# Control.net
KiCad netlist of a schematic drawn in Altium Designer
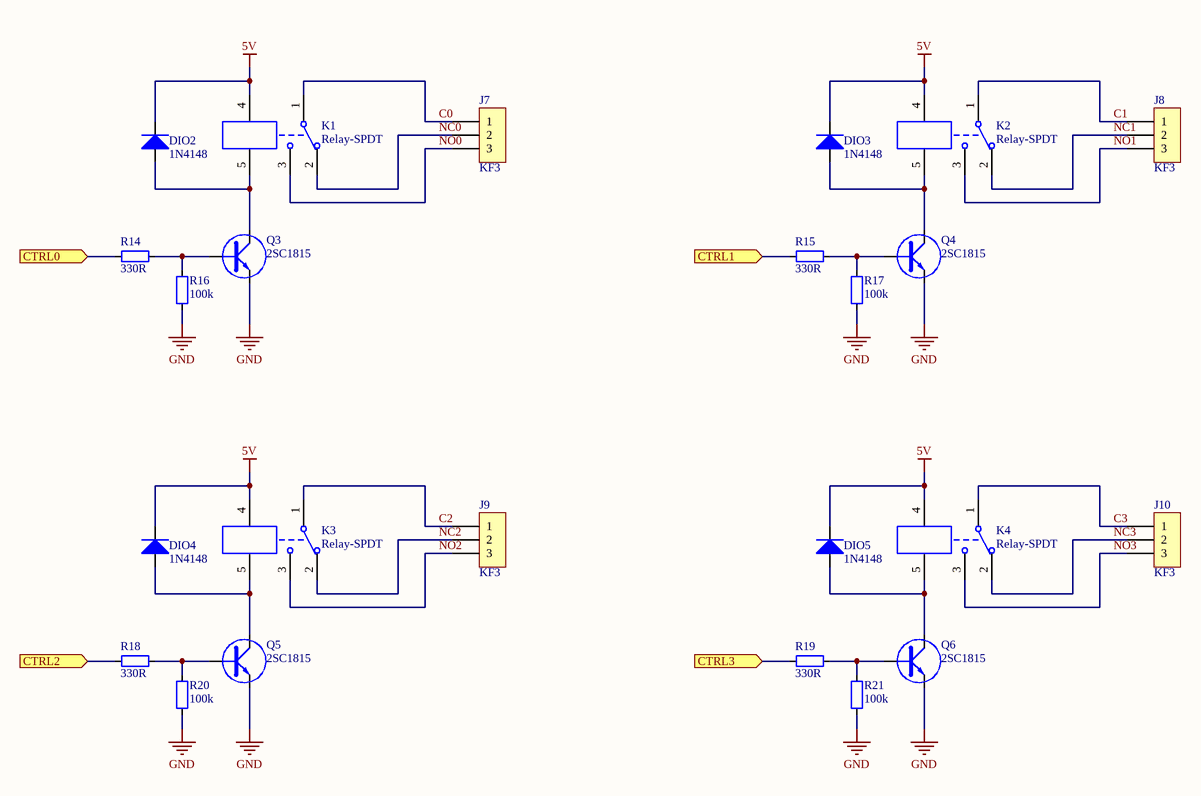
[diagram p0: Control.SchDoc]

(export (version "E")
  (design (tool "Eeschema 10.0.6"))
  (components
    (comp (ref "DIO2")
      (value "1N4148")
      (footprint "DIO-SMD-106")
      (description "Default Diode")
      (fields (field (name "PUBLISHER") "Altium Limited"))
      (libsource (lib "Ven_lib") (part "Diode SMD"))
    )
    (comp (ref "DIO3")
      (value "1N4148")
      (footprint "DIO-SMD-106")
      (description "Default Diode")
      (fields (field (name "PUBLISHER") "Altium Limited"))
      (libsource (lib "Ven_lib") (part "Diode SMD"))
    )
    (comp (ref "DIO4")
      (value "1N4148")
      (footprint "DIO-SMD-106")
      (description "Default Diode")
      (fields (field (name "PUBLISHER") "Altium Limited"))
      (libsource (lib "Ven_lib") (part "Diode SMD"))
    )
    (comp (ref "DIO5")
      (value "1N4148")
      (footprint "DIO-SMD-106")
      (description "Default Diode")
      (fields (field (name "PUBLISHER") "Altium Limited"))
      (libsource (lib "Ven_lib") (part "Diode SMD"))
    )
    (comp (ref "J7")
      (value "KF3")
      (footprint "KF3-5.08")
      (fields
        (field (name "MANUFACTURER") "Würth Elektronik eiSos GmbH")
        (field (name "PARTNO") "691103110003")
        (field (name "CREATED BY") "Karrer Zheng")
      )
      (libsource (lib "My Library") (part "KF3"))
    )
    (comp (ref "J8")
      (value "KF3")
      (footprint "KF3-5.08")
      (fields
        (field (name "MANUFACTURER") "Würth Elektronik eiSos GmbH")
        (field (name "PARTNO") "691103110003")
        (field (name "CREATED BY") "Karrer Zheng")
      )
      (libsource (lib "My Library") (part "KF3"))
    )
    (comp (ref "J9")
      (value "KF3")
      (footprint "KF3-5.08")
      (fields
        (field (name "MANUFACTURER") "Würth Elektronik eiSos GmbH")
        (field (name "PARTNO") "691103110003")
        (field (name "CREATED BY") "Karrer Zheng")
      )
      (libsource (lib "My Library") (part "KF3"))
    )
    (comp (ref "J10")
      (value "KF3")
      (footprint "KF3-5.08")
      (fields
        (field (name "MANUFACTURER") "Würth Elektronik eiSos GmbH")
        (field (name "PARTNO") "691103110003")
        (field (name "CREATED BY") "Karrer Zheng")
      )
      (libsource (lib "My Library") (part "KF3"))
    )
    (comp (ref "K1")
      (value "Relay-SPDT")
      (footprint "RELAY5PIN-10A")
      (description "Single-Pole Dual-Throw Relay")
      (fields (field (name "PUBLISHER") "Altium Limited"))
      (libsource (lib "My Library") (part "Relay-SPDT"))
    )
    (comp (ref "K2")
      (value "Relay-SPDT")
      (footprint "RELAY5PIN-10A")
      (description "Single-Pole Dual-Throw Relay")
      (fields (field (name "PUBLISHER") "Altium Limited"))
      (libsource (lib "My Library") (part "Relay-SPDT"))
    )
    (comp (ref "K3")
      (value "Relay-SPDT")
      (footprint "RELAY5PIN-10A")
      (description "Single-Pole Dual-Throw Relay")
      (fields (field (name "PUBLISHER") "Altium Limited"))
      (libsource (lib "My Library") (part "Relay-SPDT"))
    )
    (comp (ref "K4")
      (value "Relay-SPDT")
      (footprint "RELAY5PIN-10A")
      (description "Single-Pole Dual-Throw Relay")
      (fields (field (name "PUBLISHER") "Altium Limited"))
      (libsource (lib "My Library") (part "Relay-SPDT"))
    )
    (comp (ref "Q3")
      (value "2SC1815")
      (footprint "SOT23")
      (description "NPN 600mW, ECB")
      (libsource (lib "My Library") (part "2SC1815"))
    )
    (comp (ref "Q4")
      (value "2SC1815")
      (footprint "SOT23")
      (description "NPN 600mW, ECB")
      (libsource (lib "My Library") (part "2SC1815"))
    )
    (comp (ref "Q5")
      (value "2SC1815")
      (footprint "SOT23")
      (description "NPN 600mW, ECB")
      (libsource (lib "My Library") (part "2SC1815"))
    )
    (comp (ref "Q6")
      (value "2SC1815")
      (footprint "SOT23")
      (description "NPN 600mW, ECB")
      (libsource (lib "My Library") (part "2SC1815"))
    )
    (comp (ref "R14")
      (value "330R")
      (footprint "RES-SMD-0805")
      (description "Resistor")
      (fields
        (field (name "MANUFACTURER") "Generic Components")
        (field (name "PUBLISHER") "Altium Hobart Technology Centre")
      )
      (libsource (lib "My Library") (part "Resistor - SMD"))
    )
    (comp (ref "R15")
      (value "330R")
      (footprint "RES-SMD-0805")
      (description "Resistor")
      (fields
        (field (name "MANUFACTURER") "Generic Components")
        (field (name "PUBLISHER") "Altium Hobart Technology Centre")
      )
      (libsource (lib "My Library") (part "Resistor - SMD"))
    )
    (comp (ref "R16")
      (value "100k")
      (footprint "RES-SMD-0805")
      (description "Resistor")
      (fields
        (field (name "MANUFACTURER") "Generic Components")
        (field (name "PUBLISHER") "Altium Hobart Technology Centre")
      )
      (libsource (lib "My Library") (part "Resistor - SMD"))
    )
    (comp (ref "R17")
      (value "100k")
      (footprint "RES-SMD-0805")
      (description "Resistor")
      (fields
        (field (name "MANUFACTURER") "Generic Components")
        (field (name "PUBLISHER") "Altium Hobart Technology Centre")
      )
      (libsource (lib "My Library") (part "Resistor - SMD"))
    )
    (comp (ref "R18")
      (value "330R")
      (footprint "RES-SMD-0805")
      (description "Resistor")
      (fields
        (field (name "MANUFACTURER") "Generic Components")
        (field (name "PUBLISHER") "Altium Hobart Technology Centre")
      )
      (libsource (lib "My Library") (part "Resistor - SMD"))
    )
    (comp (ref "R19")
      (value "330R")
      (footprint "RES-SMD-0805")
      (description "Resistor")
      (fields
        (field (name "MANUFACTURER") "Generic Components")
        (field (name "PUBLISHER") "Altium Hobart Technology Centre")
      )
      (libsource (lib "My Library") (part "Resistor - SMD"))
    )
    (comp (ref "R20")
      (value "100k")
      (footprint "RES-SMD-0805")
      (description "Resistor")
      (fields
        (field (name "MANUFACTURER") "Generic Components")
        (field (name "PUBLISHER") "Altium Hobart Technology Centre")
      )
      (libsource (lib "My Library") (part "Resistor - SMD"))
    )
    (comp (ref "R21")
      (value "100k")
      (footprint "RES-SMD-0805")
      (description "Resistor")
      (fields
        (field (name "MANUFACTURER") "Generic Components")
        (field (name "PUBLISHER") "Altium Hobart Technology Centre")
      )
      (libsource (lib "My Library") (part "Resistor - SMD"))
    )
  )
  (nets
    (net (code "1") (name "/C0") (class "Default")
      (node (ref "J7") (pin "1") (pinfunction "1_1") (pintype "passive"))
      (node (ref "K1") (pin "1") (pinfunction "1_1") (pintype "passive"))
    )
    (net (code "2") (name "/C1") (class "Default")
      (node (ref "J8") (pin "1") (pinfunction "1_1") (pintype "passive"))
      (node (ref "K2") (pin "1") (pinfunction "1_1") (pintype "passive"))
    )
    (net (code "3") (name "/C2") (class "Default")
      (node (ref "J9") (pin "1") (pinfunction "1_1") (pintype "passive"))
      (node (ref "K3") (pin "1") (pinfunction "1_1") (pintype "passive"))
    )
    (net (code "4") (name "/C3") (class "Default")
      (node (ref "J10") (pin "1") (pinfunction "1_1") (pintype "passive"))
      (node (ref "K4") (pin "1") (pinfunction "1_1") (pintype "passive"))
    )
    (net (code "5") (name "/CTRL0") (class "Default")
      (node (ref "R14") (pin "1") (pinfunction "1_1") (pintype "passive"))
    )
    (net (code "6") (name "/CTRL1") (class "Default")
      (node (ref "R15") (pin "1") (pinfunction "1_1") (pintype "passive"))
    )
    (net (code "7") (name "/CTRL2") (class "Default")
      (node (ref "R18") (pin "1") (pinfunction "1_1") (pintype "passive"))
    )
    (net (code "8") (name "/CTRL3") (class "Default")
      (node (ref "R19") (pin "1") (pinfunction "1_1") (pintype "passive"))
    )
    (net (code "9") (name "/NC0") (class "Default")
      (node (ref "J7") (pin "2") (pinfunction "2_2") (pintype "passive"))
      (node (ref "K1") (pin "2") (pinfunction "2_2") (pintype "passive"))
    )
    (net (code "10") (name "/NC1") (class "Default")
      (node (ref "J8") (pin "2") (pinfunction "2_2") (pintype "passive"))
      (node (ref "K2") (pin "2") (pinfunction "2_2") (pintype "passive"))
    )
    (net (code "11") (name "/NC2") (class "Default")
      (node (ref "J9") (pin "2") (pinfunction "2_2") (pintype "passive"))
      (node (ref "K3") (pin "2") (pinfunction "2_2") (pintype "passive"))
    )
    (net (code "12") (name "/NC3") (class "Default")
      (node (ref "J10") (pin "2") (pinfunction "2_2") (pintype "passive"))
      (node (ref "K4") (pin "2") (pinfunction "2_2") (pintype "passive"))
    )
    (net (code "13") (name "/NO0") (class "Default")
      (node (ref "J7") (pin "3") (pinfunction "3_3") (pintype "passive"))
      (node (ref "K1") (pin "3") (pinfunction "3_3") (pintype "passive"))
    )
    (net (code "14") (name "/NO1") (class "Default")
      (node (ref "J8") (pin "3") (pinfunction "3_3") (pintype "passive"))
      (node (ref "K2") (pin "3") (pinfunction "3_3") (pintype "passive"))
    )
    (net (code "15") (name "/NO2") (class "Default")
      (node (ref "J9") (pin "3") (pinfunction "3_3") (pintype "passive"))
      (node (ref "K3") (pin "3") (pinfunction "3_3") (pintype "passive"))
    )
    (net (code "16") (name "/NO3") (class "Default")
      (node (ref "J10") (pin "3") (pinfunction "3_3") (pintype "passive"))
      (node (ref "K4") (pin "3") (pinfunction "3_3") (pintype "passive"))
    )
    (net (code "17") (name "5V") (class "Default")
      (node (ref "DIO2") (pin "2") (pinfunction "K_2") (pintype "passive"))
      (node (ref "DIO3") (pin "2") (pinfunction "K_2") (pintype "passive"))
      (node (ref "DIO4") (pin "2") (pinfunction "K_2") (pintype "passive"))
      (node (ref "DIO5") (pin "2") (pinfunction "K_2") (pintype "passive"))
      (node (ref "K1") (pin "4") (pinfunction "4_4") (pintype "passive"))
      (node (ref "K2") (pin "4") (pinfunction "4_4") (pintype "passive"))
      (node (ref "K3") (pin "4") (pinfunction "4_4") (pintype "passive"))
      (node (ref "K4") (pin "4") (pinfunction "4_4") (pintype "passive"))
    )
    (net (code "18") (name "GND") (class "Default")
      (node (ref "Q3") (pin "3") (pinfunction "E_3") (pintype "passive"))
      (node (ref "Q4") (pin "3") (pinfunction "E_3") (pintype "passive"))
      (node (ref "Q5") (pin "3") (pinfunction "E_3") (pintype "passive"))
      (node (ref "Q6") (pin "3") (pinfunction "E_3") (pintype "passive"))
      (node (ref "R16") (pin "1") (pinfunction "1_1") (pintype "passive"))
      (node (ref "R17") (pin "1") (pinfunction "1_1") (pintype "passive"))
      (node (ref "R20") (pin "1") (pinfunction "1_1") (pintype "passive"))
      (node (ref "R21") (pin "1") (pinfunction "1_1") (pintype "passive"))
    )
    (net (code "19") (name "Net-(DIO2-A)") (class "Default")
      (node (ref "DIO2") (pin "1") (pinfunction "A_1") (pintype "passive"))
      (node (ref "K1") (pin "5") (pinfunction "5_5") (pintype "passive"))
      (node (ref "Q3") (pin "2") (pinfunction "C_2") (pintype "passive"))
    )
    (net (code "20") (name "Net-(DIO3-A)") (class "Default")
      (node (ref "DIO3") (pin "1") (pinfunction "A_1") (pintype "passive"))
      (node (ref "K2") (pin "5") (pinfunction "5_5") (pintype "passive"))
      (node (ref "Q4") (pin "2") (pinfunction "C_2") (pintype "passive"))
    )
    (net (code "21") (name "Net-(DIO4-A)") (class "Default")
      (node (ref "DIO4") (pin "1") (pinfunction "A_1") (pintype "passive"))
      (node (ref "K3") (pin "5") (pinfunction "5_5") (pintype "passive"))
      (node (ref "Q5") (pin "2") (pinfunction "C_2") (pintype "passive"))
    )
    (net (code "22") (name "Net-(DIO5-A)") (class "Default")
      (node (ref "DIO5") (pin "1") (pinfunction "A_1") (pintype "passive"))
      (node (ref "K4") (pin "5") (pinfunction "5_5") (pintype "passive"))
      (node (ref "Q6") (pin "2") (pinfunction "C_2") (pintype "passive"))
    )
    (net (code "23") (name "Net-(Q3-B)") (class "Default")
      (node (ref "Q3") (pin "1") (pinfunction "B_1") (pintype "passive"))
      (node (ref "R14") (pin "2") (pinfunction "2_2") (pintype "passive"))
      (node (ref "R16") (pin "2") (pinfunction "2_2") (pintype "passive"))
    )
    (net (code "24") (name "Net-(Q4-B)") (class "Default")
      (node (ref "Q4") (pin "1") (pinfunction "B_1") (pintype "passive"))
      (node (ref "R15") (pin "2") (pinfunction "2_2") (pintype "passive"))
      (node (ref "R17") (pin "2") (pinfunction "2_2") (pintype "passive"))
    )
    (net (code "25") (name "Net-(Q5-B)") (class "Default")
      (node (ref "Q5") (pin "1") (pinfunction "B_1") (pintype "passive"))
      (node (ref "R18") (pin "2") (pinfunction "2_2") (pintype "passive"))
      (node (ref "R20") (pin "2") (pinfunction "2_2") (pintype "passive"))
    )
    (net (code "26") (name "Net-(Q6-B)") (class "Default")
      (node (ref "Q6") (pin "1") (pinfunction "B_1") (pintype "passive"))
      (node (ref "R19") (pin "2") (pinfunction "2_2") (pintype "passive"))
      (node (ref "R21") (pin "2") (pinfunction "2_2") (pintype "passive"))
    )
  )
)
